# LEDARRAYLOW.net
KiCad netlist of a schematic drawn in EAGLE
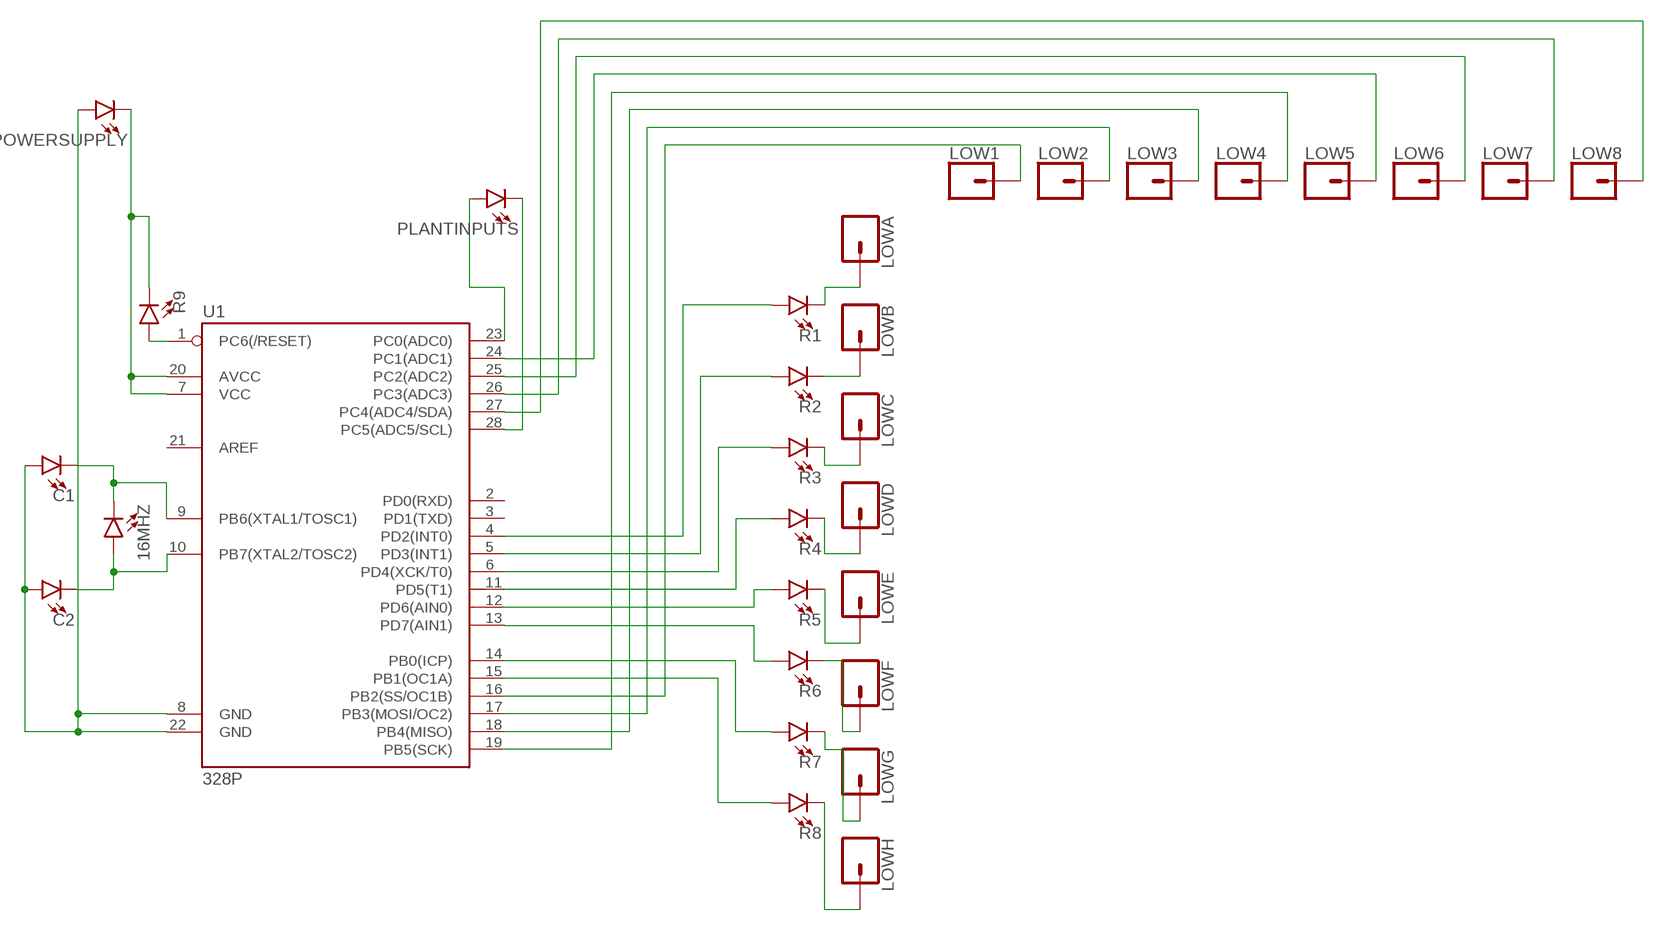
[diagram p0: schematic, sheet 1]

(export (version "E")
  (design (tool "Eeschema 10.0.6"))
  (components
    (comp (ref "16MHZ")
      (value "LED3MM")
      (footprint "eagle-import:LED_3MM")
      (libsource (lib "eagle-import") (part "LED3MM"))
    )
    (comp (ref "C1")
      (value "LED3MM")
      (footprint "eagle-import:LED_3MM")
      (libsource (lib "eagle-import") (part "LED3MM"))
    )
    (comp (ref "C2")
      (value "LED3MM")
      (footprint "eagle-import:LED_3MM")
      (libsource (lib "eagle-import") (part "LED3MM"))
    )
    (comp (ref "LOW1")
      (value "CONN_01PTH_NO_SILK_KIT")
      (footprint "eagle-import:1X01NS_KIT")
      (libsource (lib "eagle-import") (part "CONN_01PTH_NO_SILK_KIT"))
    )
    (comp (ref "LOW2")
      (value "CONN_01PTH_NO_SILK_KIT")
      (footprint "eagle-import:1X01NS_KIT")
      (libsource (lib "eagle-import") (part "CONN_01PTH_NO_SILK_KIT"))
    )
    (comp (ref "LOW3")
      (value "CONN_01PTH_NO_SILK_KIT")
      (footprint "eagle-import:1X01NS_KIT")
      (libsource (lib "eagle-import") (part "CONN_01PTH_NO_SILK_KIT"))
    )
    (comp (ref "LOW4")
      (value "CONN_01PTH_NO_SILK_KIT")
      (footprint "eagle-import:1X01NS_KIT")
      (libsource (lib "eagle-import") (part "CONN_01PTH_NO_SILK_KIT"))
    )
    (comp (ref "LOW5")
      (value "CONN_01PTH_NO_SILK_KIT")
      (footprint "eagle-import:1X01NS_KIT")
      (libsource (lib "eagle-import") (part "CONN_01PTH_NO_SILK_KIT"))
    )
    (comp (ref "LOW6")
      (value "CONN_01PTH_NO_SILK_KIT")
      (footprint "eagle-import:1X01NS_KIT")
      (libsource (lib "eagle-import") (part "CONN_01PTH_NO_SILK_KIT"))
    )
    (comp (ref "LOW7")
      (value "CONN_01PTH_NO_SILK_KIT")
      (footprint "eagle-import:1X01NS_KIT")
      (libsource (lib "eagle-import") (part "CONN_01PTH_NO_SILK_KIT"))
    )
    (comp (ref "LOW8")
      (value "CONN_01PTH_NO_SILK_KIT")
      (footprint "eagle-import:1X01NS_KIT")
      (libsource (lib "eagle-import") (part "CONN_01PTH_NO_SILK_KIT"))
    )
    (comp (ref "LOWA")
      (value "CONN_01PTH_NO_SILK_KIT")
      (footprint "eagle-import:1X01NS_KIT")
      (libsource (lib "eagle-import") (part "CONN_01PTH_NO_SILK_KIT"))
    )
    (comp (ref "LOWB")
      (value "CONN_01PTH_NO_SILK_KIT")
      (footprint "eagle-import:1X01NS_KIT")
      (libsource (lib "eagle-import") (part "CONN_01PTH_NO_SILK_KIT"))
    )
    (comp (ref "LOWC")
      (value "CONN_01PTH_NO_SILK_KIT")
      (footprint "eagle-import:1X01NS_KIT")
      (libsource (lib "eagle-import") (part "CONN_01PTH_NO_SILK_KIT"))
    )
    (comp (ref "LOWD")
      (value "CONN_01PTH_NO_SILK_KIT")
      (footprint "eagle-import:1X01NS_KIT")
      (libsource (lib "eagle-import") (part "CONN_01PTH_NO_SILK_KIT"))
    )
    (comp (ref "LOWE")
      (value "CONN_01PTH_NO_SILK_KIT")
      (footprint "eagle-import:1X01NS_KIT")
      (libsource (lib "eagle-import") (part "CONN_01PTH_NO_SILK_KIT"))
    )
    (comp (ref "LOWF")
      (value "CONN_01PTH_NO_SILK_KIT")
      (footprint "eagle-import:1X01NS_KIT")
      (libsource (lib "eagle-import") (part "CONN_01PTH_NO_SILK_KIT"))
    )
    (comp (ref "LOWG")
      (value "CONN_01PTH_NO_SILK_KIT")
      (footprint "eagle-import:1X01NS_KIT")
      (libsource (lib "eagle-import") (part "CONN_01PTH_NO_SILK_KIT"))
    )
    (comp (ref "LOWH")
      (value "CONN_01PTH_NO_SILK_KIT")
      (footprint "eagle-import:1X01NS_KIT")
      (libsource (lib "eagle-import") (part "CONN_01PTH_NO_SILK_KIT"))
    )
    (comp (ref "PLANTINPUTS")
      (value "LED3MM")
      (footprint "eagle-import:LED_3MM")
      (libsource (lib "eagle-import") (part "LED3MM"))
    )
    (comp (ref "POWERSUPPLY")
      (value "LED3MM")
      (footprint "eagle-import:LED_3MM")
      (libsource (lib "eagle-import") (part "LED3MM"))
    )
    (comp (ref "R1")
      (value "LED3MM")
      (footprint "eagle-import:LED_3MM")
      (libsource (lib "eagle-import") (part "LED3MM"))
    )
    (comp (ref "R2")
      (value "LED3MM")
      (footprint "eagle-import:LED_3MM")
      (libsource (lib "eagle-import") (part "LED3MM"))
    )
    (comp (ref "R3")
      (value "LED3MM")
      (footprint "eagle-import:LED_3MM")
      (libsource (lib "eagle-import") (part "LED3MM"))
    )
    (comp (ref "R4")
      (value "LED3MM")
      (footprint "eagle-import:LED_3MM")
      (libsource (lib "eagle-import") (part "LED3MM"))
    )
    (comp (ref "R5")
      (value "LED3MM")
      (footprint "eagle-import:LED_3MM")
      (libsource (lib "eagle-import") (part "LED3MM"))
    )
    (comp (ref "R6")
      (value "LED3MM")
      (footprint "eagle-import:LED_3MM")
      (libsource (lib "eagle-import") (part "LED3MM"))
    )
    (comp (ref "R7")
      (value "LED3MM")
      (footprint "eagle-import:LED_3MM")
      (libsource (lib "eagle-import") (part "LED3MM"))
    )
    (comp (ref "R8")
      (value "LED3MM")
      (footprint "eagle-import:LED_3MM")
      (libsource (lib "eagle-import") (part "LED3MM"))
    )
    (comp (ref "R9")
      (value "LED3MM")
      (footprint "eagle-import:LED_3MM")
      (libsource (lib "eagle-import") (part "LED3MM"))
    )
    (comp (ref "U1")
      (value "328P")
      (footprint "eagle-import:DIP28")
      (libsource (lib "eagle-import") (part "ATMEGA328P_PDIP"))
    )
  )
  (nets
    (net (code "1") (name "Net-(16MHZ-C)") (class "Default")
      (node (ref "16MHZ") (pin "K") (pinfunction "C_K") (pintype "passive"))
      (node (ref "C1") (pin "K") (pinfunction "C_K") (pintype "passive"))
      (node (ref "U1") (pin "9") (pinfunction "PB6(XTAL1/TOSC1)_9") (pintype "bidirectional"))
    )
    (net (code "2") (name "Net-(C1-PadA)") (class "Default")
      (node (ref "C1") (pin "A") (pinfunction "A_A") (pintype "passive"))
      (node (ref "C2") (pin "A") (pinfunction "A_A") (pintype "passive"))
      (node (ref "POWERSUPPLY") (pin "A") (pinfunction "A_A") (pintype "passive"))
      (node (ref "U1") (pin "22") (pinfunction "GND_22") (pintype "bidirectional"))
      (node (ref "U1") (pin "8") (pinfunction "GND_8") (pintype "bidirectional"))
    )
    (net (code "3") (name "Net-(C2-C)") (class "Default")
      (node (ref "16MHZ") (pin "A") (pinfunction "A_A") (pintype "passive"))
      (node (ref "C2") (pin "K") (pinfunction "C_K") (pintype "passive"))
      (node (ref "U1") (pin "10") (pinfunction "PB7(XTAL2/TOSC2)_10") (pintype "bidirectional"))
    )
    (net (code "4") (name "Net-(PLANTINPUTS-C)") (class "Default")
      (node (ref "PLANTINPUTS") (pin "K") (pinfunction "C_K") (pintype "passive"))
      (node (ref "U1") (pin "28") (pinfunction "PC5(ADC5/SCL)_28") (pintype "bidirectional"))
    )
    (net (code "5") (name "Net-(POWERSUPPLY-C)") (class "Default")
      (node (ref "POWERSUPPLY") (pin "K") (pinfunction "C_K") (pintype "passive"))
      (node (ref "R9") (pin "K") (pinfunction "C_K") (pintype "passive"))
      (node (ref "U1") (pin "20") (pinfunction "AVCC_20") (pintype "bidirectional"))
      (node (ref "U1") (pin "7") (pinfunction "VCC_7") (pintype "bidirectional"))
    )
    (net (code "6") (name "Net-(R1-C)") (class "Default")
      (node (ref "LOWA") (pin "1") (pinfunction "1_1") (pintype "passive"))
      (node (ref "R1") (pin "K") (pinfunction "C_K") (pintype "passive"))
    )
    (net (code "7") (name "Net-(R2-C)") (class "Default")
      (node (ref "LOWB") (pin "1") (pinfunction "1_1") (pintype "passive"))
      (node (ref "R2") (pin "K") (pinfunction "C_K") (pintype "passive"))
    )
    (net (code "8") (name "Net-(R3-C)") (class "Default")
      (node (ref "LOWC") (pin "1") (pinfunction "1_1") (pintype "passive"))
      (node (ref "R3") (pin "K") (pinfunction "C_K") (pintype "passive"))
    )
    (net (code "9") (name "Net-(R4-C)") (class "Default")
      (node (ref "LOWD") (pin "1") (pinfunction "1_1") (pintype "passive"))
      (node (ref "R4") (pin "K") (pinfunction "C_K") (pintype "passive"))
    )
    (net (code "10") (name "Net-(R5-C)") (class "Default")
      (node (ref "LOWE") (pin "1") (pinfunction "1_1") (pintype "passive"))
      (node (ref "R5") (pin "K") (pinfunction "C_K") (pintype "passive"))
    )
    (net (code "11") (name "Net-(R6-C)") (class "Default")
      (node (ref "LOWF") (pin "1") (pinfunction "1_1") (pintype "passive"))
      (node (ref "R6") (pin "K") (pinfunction "C_K") (pintype "passive"))
    )
    (net (code "12") (name "Net-(R7-C)") (class "Default")
      (node (ref "LOWG") (pin "1") (pinfunction "1_1") (pintype "passive"))
      (node (ref "R7") (pin "K") (pinfunction "C_K") (pintype "passive"))
    )
    (net (code "13") (name "Net-(R8-C)") (class "Default")
      (node (ref "LOWH") (pin "1") (pinfunction "1_1") (pintype "passive"))
      (node (ref "R8") (pin "K") (pinfunction "C_K") (pintype "passive"))
    )
    (net (code "14") (name "Net-(U1-PB0(ICP))") (class "Default")
      (node (ref "R7") (pin "A") (pinfunction "A_A") (pintype "passive"))
      (node (ref "U1") (pin "14") (pinfunction "PB0(ICP)_14") (pintype "bidirectional"))
    )
    (net (code "15") (name "Net-(U1-PB1(OC1A))") (class "Default")
      (node (ref "R8") (pin "A") (pinfunction "A_A") (pintype "passive"))
      (node (ref "U1") (pin "15") (pinfunction "PB1(OC1A)_15") (pintype "bidirectional"))
    )
    (net (code "16") (name "Net-(U1-PB2(SS{slash}OC1B))") (class "Default")
      (node (ref "LOW1") (pin "1") (pinfunction "1_1") (pintype "passive"))
      (node (ref "U1") (pin "16") (pinfunction "PB2(SS/OC1B)_16") (pintype "bidirectional"))
    )
    (net (code "17") (name "Net-(U1-PB3(MOSI{slash}OC2))") (class "Default")
      (node (ref "LOW2") (pin "1") (pinfunction "1_1") (pintype "passive"))
      (node (ref "U1") (pin "17") (pinfunction "PB3(MOSI/OC2)_17") (pintype "bidirectional"))
    )
    (net (code "18") (name "Net-(U1-PB4(MISO))") (class "Default")
      (node (ref "LOW3") (pin "1") (pinfunction "1_1") (pintype "passive"))
      (node (ref "U1") (pin "18") (pinfunction "PB4(MISO)_18") (pintype "bidirectional"))
    )
    (net (code "19") (name "Net-(U1-PB5(SCK))") (class "Default")
      (node (ref "LOW4") (pin "1") (pinfunction "1_1") (pintype "passive"))
      (node (ref "U1") (pin "19") (pinfunction "PB5(SCK)_19") (pintype "bidirectional"))
    )
    (net (code "20") (name "Net-(U1-PC0(ADC0))") (class "Default")
      (node (ref "PLANTINPUTS") (pin "A") (pinfunction "A_A") (pintype "passive"))
      (node (ref "U1") (pin "23") (pinfunction "PC0(ADC0)_23") (pintype "bidirectional"))
    )
    (net (code "21") (name "Net-(U1-PC1(ADC1))") (class "Default")
      (node (ref "LOW5") (pin "1") (pinfunction "1_1") (pintype "passive"))
      (node (ref "U1") (pin "24") (pinfunction "PC1(ADC1)_24") (pintype "bidirectional"))
    )
    (net (code "22") (name "Net-(U1-PC2(ADC2))") (class "Default")
      (node (ref "LOW6") (pin "1") (pinfunction "1_1") (pintype "passive"))
      (node (ref "U1") (pin "25") (pinfunction "PC2(ADC2)_25") (pintype "bidirectional"))
    )
    (net (code "23") (name "Net-(U1-PC3(ADC3))") (class "Default")
      (node (ref "LOW7") (pin "1") (pinfunction "1_1") (pintype "passive"))
      (node (ref "U1") (pin "26") (pinfunction "PC3(ADC3)_26") (pintype "bidirectional"))
    )
    (net (code "24") (name "Net-(U1-PC4(ADC4{slash}SDA))") (class "Default")
      (node (ref "LOW8") (pin "1") (pinfunction "1_1") (pintype "passive"))
      (node (ref "U1") (pin "27") (pinfunction "PC4(ADC4/SDA)_27") (pintype "bidirectional"))
    )
    (net (code "25") (name "Net-(U1-PC6({slash}RESET))") (class "Default")
      (node (ref "R9") (pin "A") (pinfunction "A_A") (pintype "passive"))
      (node (ref "U1") (pin "1") (pinfunction "PC6(/RESET)_1") (pintype "bidirectional"))
    )
    (net (code "26") (name "Net-(U1-PD2(INT0))") (class "Default")
      (node (ref "R1") (pin "A") (pinfunction "A_A") (pintype "passive"))
      (node (ref "U1") (pin "4") (pinfunction "PD2(INT0)_4") (pintype "bidirectional"))
    )
    (net (code "27") (name "Net-(U1-PD3(INT1))") (class "Default")
      (node (ref "R2") (pin "A") (pinfunction "A_A") (pintype "passive"))
      (node (ref "U1") (pin "5") (pinfunction "PD3(INT1)_5") (pintype "bidirectional"))
    )
    (net (code "28") (name "Net-(U1-PD4(XCK{slash}T0))") (class "Default")
      (node (ref "R3") (pin "A") (pinfunction "A_A") (pintype "passive"))
      (node (ref "U1") (pin "6") (pinfunction "PD4(XCK/T0)_6") (pintype "bidirectional"))
    )
    (net (code "29") (name "Net-(U1-PD5(T1))") (class "Default")
      (node (ref "R4") (pin "A") (pinfunction "A_A") (pintype "passive"))
      (node (ref "U1") (pin "11") (pinfunction "PD5(T1)_11") (pintype "bidirectional"))
    )
    (net (code "30") (name "Net-(U1-PD6(AIN0))") (class "Default")
      (node (ref "R5") (pin "A") (pinfunction "A_A") (pintype "passive"))
      (node (ref "U1") (pin "12") (pinfunction "PD6(AIN0)_12") (pintype "bidirectional"))
    )
    (net (code "31") (name "Net-(U1-PD7(AIN1))") (class "Default")
      (node (ref "R6") (pin "A") (pinfunction "A_A") (pintype "passive"))
      (node (ref "U1") (pin "13") (pinfunction "PD7(AIN1)_13") (pintype "bidirectional"))
    )
    (net (code "32") (name "unconnected-(U1-AREF-Pad21)") (class "Default")
      (node (ref "U1") (pin "21") (pinfunction "AREF_21") (pintype "bidirectional"))
    )
    (net (code "33") (name "unconnected-(U1-PD0(RXD)-Pad2)") (class "Default")
      (node (ref "U1") (pin "2") (pinfunction "PD0(RXD)_2") (pintype "bidirectional"))
    )
    (net (code "34") (name "unconnected-(U1-PD1(TXD)-Pad3)") (class "Default")
      (node (ref "U1") (pin "3") (pinfunction "PD1(TXD)_3") (pintype "bidirectional"))
    )
  )
)
